# MPU6050.net
KiCad netlist of a schematic drawn in Altium Designer
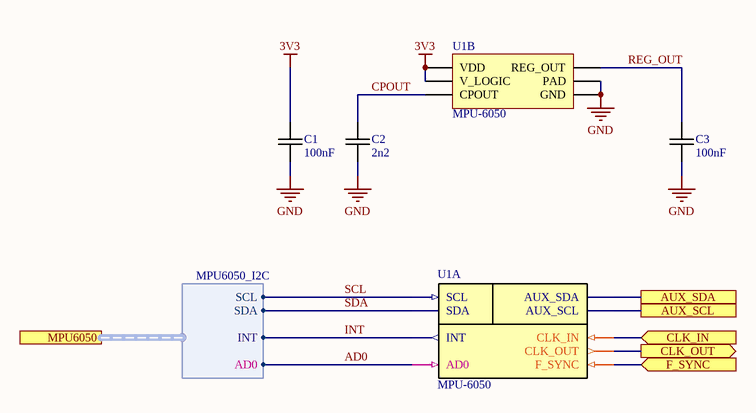
[diagram p0: MPU6050.SchDoc]

(export (version "E")
  (design (tool "Eeschema 10.0.6"))
  (components
    (comp (ref "C1")
      (value "100nF")
      (footprint "0603C-GENERIC")
      (description "CAPACITOR 0603 CERAMIC")
      (fields (field (name "TOLERANCE") "±10%") (field (name "MANUFACTURER PART NUMBER") "C1608X7R1H103K"))
      (libsource (lib "vh_altium_library") (part "0603C-100NF-50V-X7R-TDK"))
    )
    (comp (ref "C2")
      (value "2n2")
      (footprint "0603C-GENERIC")
      (description "CAPACITOR 0603 CERAMIC")
      (libsource (lib "vh_altium_library") (part "0603C-2N2-50V-C0G-MUR"))
    )
    (comp (ref "C3")
      (value "100nF")
      (footprint "0603C-GENERIC")
      (description "CAPACITOR 0603 CERAMIC")
      (fields (field (name "TOLERANCE") "±10%") (field (name "MANUFACTURER PART NUMBER") "C1608X7R1H103K"))
      (libsource (lib "vh_altium_library") (part "0603C-100NF-50V-X7R-TDK"))
    )
    (comp (ref "U1")
      (value "MPU-6050")
      (footprint "QFN24")
      (description "Integrated 6-axis 3D accelerometer I2c interface")
      (libsource (lib "MyLibAltium_v1") (part "MPU-6050"))
    )
  )
  (nets
    (net (code "2") (name "/AD0") (class "Default")
      (node (ref "U1") (pin "9") (pinfunction "AD0_9") (pintype "input"))
    )
    (net (code "3") (name "/AUX_SCL") (class "Default")
      (node (ref "U1") (pin "7") (pinfunction "AUX_SCL_7") (pintype "open_collector"))
    )
    (net (code "4") (name "/AUX_SDA") (class "Default")
      (node (ref "U1") (pin "6") (pinfunction "AUX_SDA_6") (pintype "open_collector"))
    )
    (net (code "5") (name "/CLK_IN") (class "Default")
      (node (ref "U1") (pin "1") (pinfunction "CLK_IN_1") (pintype "input"))
    )
    (net (code "6") (name "/CLK_OUT") (class "Default")
      (node (ref "U1") (pin "22") (pinfunction "CLK_OUT_22") (pintype "output"))
    )
    (net (code "7") (name "/CPOUT") (class "Default")
      (node (ref "C2") (pin "2") (pintype "passive"))
      (node (ref "U1") (pin "20") (pinfunction "CPOUT_20") (pintype "power_in"))
    )
    (net (code "8") (name "/F_SYNC") (class "Default")
      (node (ref "U1") (pin "11") (pinfunction "F_SYNC_11") (pintype "input"))
    )
    (net (code "9") (name "/INT") (class "Default")
      (node (ref "U1") (pin "12") (pinfunction "INT_12") (pintype "output"))
    )
    (net (code "10") (name "/REG_OUT") (class "Default")
      (node (ref "C3") (pin "2") (pintype "passive"))
      (node (ref "U1") (pin "10") (pinfunction "REG_OUT_10") (pintype "power_in"))
    )
    (net (code "11") (name "/SCL") (class "Default")
      (node (ref "U1") (pin "23") (pinfunction "SCL_23") (pintype "input"))
    )
    (net (code "12") (name "/SDA") (class "Default")
      (node (ref "U1") (pin "24") (pinfunction "SDA_24") (pintype "open_collector"))
    )
    (net (code "14") (name "3V3") (class "Default")
      (node (ref "C1") (pin "2") (pintype "passive"))
      (node (ref "U1") (pin "13") (pinfunction "VDD_13") (pintype "power_in"))
      (node (ref "U1") (pin "8") (pinfunction "V_LOGIC_8") (pintype "power_in"))
    )
    (net (code "15") (name "GND") (class "Default")
      (node (ref "C1") (pin "1") (pintype "passive"))
      (node (ref "C2") (pin "1") (pintype "passive"))
      (node (ref "C3") (pin "1") (pintype "passive"))
      (node (ref "U1") (pin "18") (pinfunction "GND_18") (pintype "power_in"))
      (node (ref "U1") (pin "25") (pinfunction "PAD_25") (pintype "power_in"))
    )
  )
)
